# FEV-60_IO_Board.net
KiCad netlist of a schematic drawn in Altium Designer
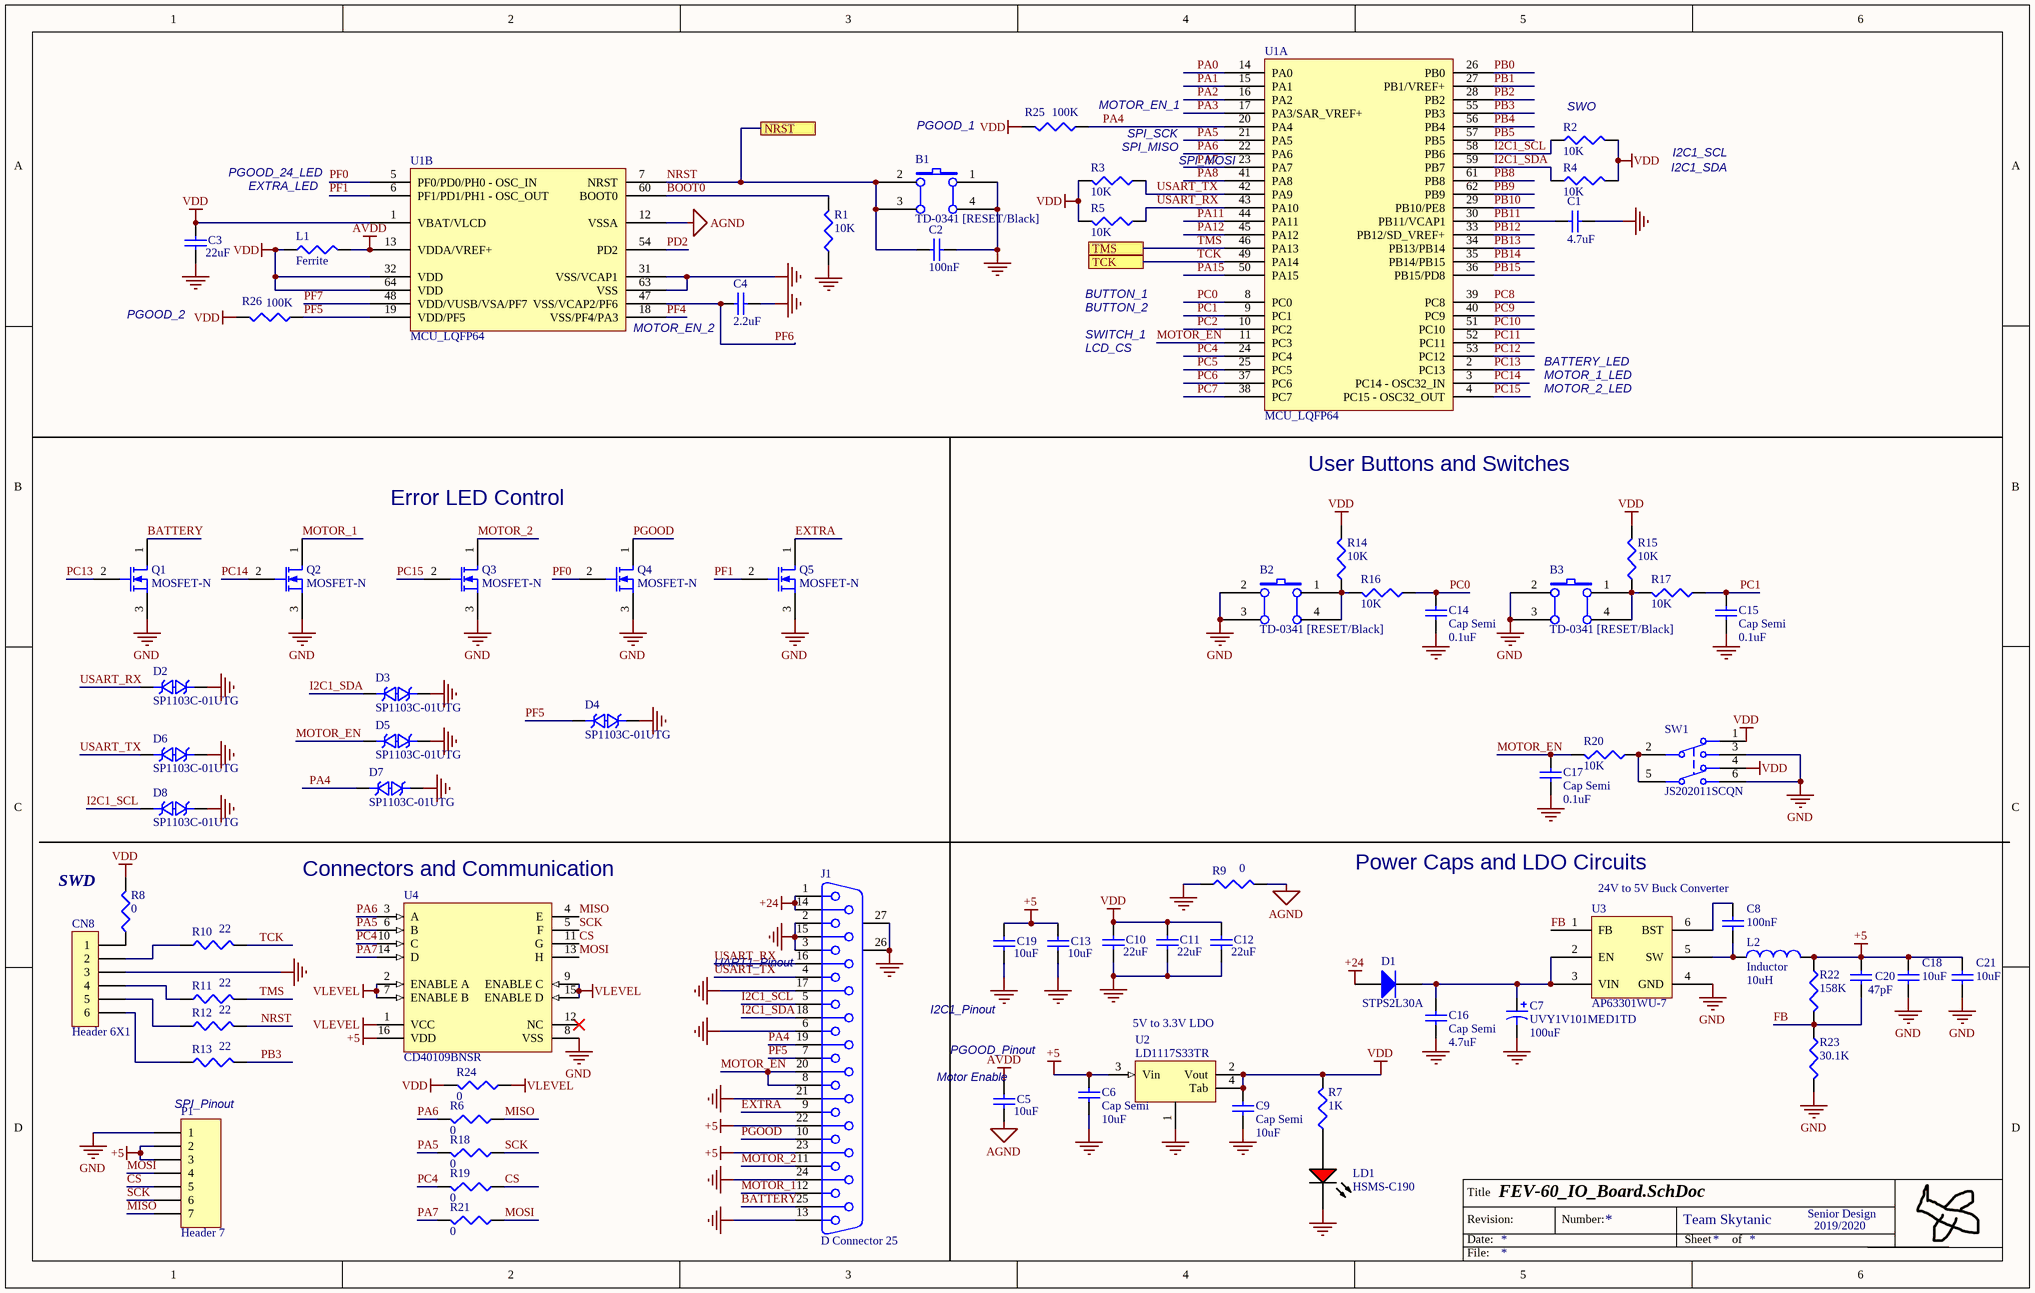
[diagram p0: FEV-60_IO_Board.SchDoc]

(export (version "E")
  (design (tool "Eeschema 10.0.6"))
  (components
    (comp (ref "B1")
      (value "TD-0341 [RESET/Black]")
      (footprint "Button")
      (description "SE PUSHBUTTON")
      (libsource (lib "Documents") (part "SW PUSHBUTTON"))
    )
    (comp (ref "B2")
      (value "TD-0341 [RESET/Black]")
      (footprint "Button")
      (description "SE PUSHBUTTON")
      (libsource (lib "Documents") (part "SW PUSHBUTTON"))
    )
    (comp (ref "B3")
      (value "TD-0341 [RESET/Black]")
      (footprint "Button")
      (description "SE PUSHBUTTON")
      (libsource (lib "Documents") (part "SW PUSHBUTTON"))
    )
    (comp (ref "C1")
      (value "4.7uF")
      (footprint "1608[0603]")
      (description "Capacitor (Semiconductor SIM Model)")
      (fields (field (name "Comment") "Cap Semi") (field (name "PUBLISHER") "Altium Limited"))
      (libsource (lib "Miscellaneous Devices") (part "Cap Semi"))
    )
    (comp (ref "C2")
      (value "100nF")
      (footprint "1608[0603]")
      (description "Capacitor (Semiconductor SIM Model)")
      (fields (field (name "Comment") "Cap Semi") (field (name "PUBLISHER") "Altium Limited"))
      (libsource (lib "Miscellaneous Devices") (part "Cap Semi"))
    )
    (comp (ref "C3")
      (value "22uF")
      (footprint "1608[0603]")
      (description "Capacitor (Semiconductor SIM Model)")
      (fields (field (name "Comment") "Cap Semi") (field (name "PUBLISHER") "Altium Limited"))
      (libsource (lib "Miscellaneous Devices") (part "Cap Semi"))
    )
    (comp (ref "C4")
      (value "2.2uF")
      (footprint "1608[0603]")
      (description "Capacitor (Semiconductor SIM Model)")
      (fields (field (name "Comment") "Cap Semi") (field (name "PUBLISHER") "Altium Limited"))
      (libsource (lib "Miscellaneous Devices") (part "Cap Semi"))
    )
    (comp (ref "C5")
      (value "10uF")
      (footprint "1608[0603]")
      (description "Capacitor (Semiconductor SIM Model)")
      (fields (field (name "Comment") "Cap Semi") (field (name "PUBLISHER") "Altium Limited"))
      (libsource (lib "Miscellaneous Devices") (part "Cap Semi"))
    )
    (comp (ref "C6")
      (value "Cap Semi")
      (footprint "1608[0603]")
      (description "Capacitor (Semiconductor SIM Model)")
      (fields (field (name "ALTIUM_VALUE") "10uF") (field (name "PUBLISHER") "Altium Limited"))
      (libsource (lib "Miscellaneous Devices") (part "Cap Semi"))
    )
    (comp (ref "C7")
      (value "UVY1V101MED1TD")
      (footprint "UVY1V101MED1TD")
      (description "Polarized Capacitor (Axial)")
      (fields (field (name "ALTIUM_VALUE") "100uF") (field (name "PUBLISHER") "Altium Limited"))
      (libsource (lib "FEV-60_Lib") (part "UVY1V101MED1TD"))
    )
    (comp (ref "C8")
      (value "100nF")
      (footprint "1608[0603]")
      (description "Capacitor (Semiconductor SIM Model)")
      (fields (field (name "Comment") "Cap Semi") (field (name "PUBLISHER") "Altium Limited"))
      (libsource (lib "Miscellaneous Devices") (part "Cap Semi"))
    )
    (comp (ref "C9")
      (value "Cap Semi")
      (footprint "1608[0603]")
      (description "Capacitor (Semiconductor SIM Model)")
      (fields (field (name "ALTIUM_VALUE") "10uF") (field (name "PUBLISHER") "Altium Limited"))
      (libsource (lib "Miscellaneous Devices") (part "Cap Semi"))
    )
    (comp (ref "C10")
      (value "22uF")
      (footprint "1608[0603]")
      (description "Capacitor (Semiconductor SIM Model)")
      (fields (field (name "Comment") "Cap Semi") (field (name "PUBLISHER") "Altium Limited"))
      (libsource (lib "Miscellaneous Devices") (part "Cap Semi"))
    )
    (comp (ref "C11")
      (value "22uF")
      (footprint "1608[0603]")
      (description "Capacitor (Semiconductor SIM Model)")
      (fields (field (name "Comment") "Cap Semi") (field (name "PUBLISHER") "Altium Limited"))
      (libsource (lib "Miscellaneous Devices") (part "Cap Semi"))
    )
    (comp (ref "C12")
      (value "22uF")
      (footprint "1608[0603]")
      (description "Capacitor (Semiconductor SIM Model)")
      (fields (field (name "Comment") "Cap Semi") (field (name "PUBLISHER") "Altium Limited"))
      (libsource (lib "Miscellaneous Devices") (part "Cap Semi"))
    )
    (comp (ref "C13")
      (value "10uF")
      (footprint "1608[0603]")
      (description "Capacitor (Semiconductor SIM Model)")
      (fields (field (name "Comment") "Cap Semi") (field (name "PUBLISHER") "Altium Limited"))
      (libsource (lib "Miscellaneous Devices") (part "Cap Semi"))
    )
    (comp (ref "C14")
      (value "Cap Semi")
      (footprint "1608[0603]")
      (description "Capacitor (Semiconductor SIM Model)")
      (fields (field (name "ALTIUM_VALUE") "0.1uF") (field (name "PUBLISHER") "Altium Limited"))
      (libsource (lib "Miscellaneous Devices") (part "Cap Semi"))
    )
    (comp (ref "C15")
      (value "Cap Semi")
      (footprint "1608[0603]")
      (description "Capacitor (Semiconductor SIM Model)")
      (fields (field (name "ALTIUM_VALUE") "0.1uF") (field (name "PUBLISHER") "Altium Limited"))
      (libsource (lib "Miscellaneous Devices") (part "Cap Semi"))
    )
    (comp (ref "C16")
      (value "Cap Semi")
      (footprint "1608[0603]")
      (description "Capacitor (Semiconductor SIM Model)")
      (fields (field (name "ALTIUM_VALUE") "4.7uF") (field (name "PUBLISHER") "Altium Limited"))
      (libsource (lib "Miscellaneous Devices") (part "Cap Semi"))
    )
    (comp (ref "C17")
      (value "Cap Semi")
      (footprint "1608[0603]")
      (description "Capacitor (Semiconductor SIM Model)")
      (fields (field (name "ALTIUM_VALUE") "0.1uF") (field (name "PUBLISHER") "Altium Limited"))
      (libsource (lib "Miscellaneous Devices") (part "Cap Semi"))
    )
    (comp (ref "C18")
      (value "10uF")
      (footprint "1608[0603]")
      (description "Capacitor (Semiconductor SIM Model)")
      (fields (field (name "Comment") "Cap Semi") (field (name "PUBLISHER") "Altium Limited"))
      (libsource (lib "Miscellaneous Devices") (part "Cap Semi"))
    )
    (comp (ref "C19")
      (value "10uF")
      (footprint "1608[0603]")
      (description "Capacitor (Semiconductor SIM Model)")
      (fields (field (name "Comment") "Cap Semi") (field (name "PUBLISHER") "Altium Limited"))
      (libsource (lib "Miscellaneous Devices") (part "Cap Semi"))
    )
    (comp (ref "C20")
      (value "47pF")
      (footprint "1608[0603]")
      (description "Capacitor (Semiconductor SIM Model)")
      (fields (field (name "Comment") "Cap Semi") (field (name "PUBLISHER") "Altium Limited"))
      (libsource (lib "Miscellaneous Devices") (part "Cap Semi"))
    )
    (comp (ref "C21")
      (value "10uF")
      (footprint "1608[0603]")
      (description "Capacitor (Semiconductor SIM Model)")
      (fields (field (name "Comment") "Cap Semi") (field (name "PUBLISHER") "Altium Limited"))
      (libsource (lib "Miscellaneous Devices") (part "Cap Semi"))
    )
    (comp (ref "CN8")
      (value "Header 6X1")
      (footprint "HDR1X6")
      (description "Header, 6-Pin, Single row")
      (fields (field (name "PUBLISHER") "Altium Limited"))
      (libsource (lib "Nucleo_64") (part "Header 6X1"))
    )
    (comp (ref "D1")
      (value "STPS2L30A")
      (footprint "STPS2L30A")
      (libsource (lib "Nucleo_64") (part "STPS2L30A"))
    )
    (comp (ref "D2")
      (value "SP1103C-01UTG")
      (footprint "SP1103C-01UTG")
      (description "9V (Typ) Clamp 80A (8/20µs) Ipp Tvs Diode Surface Mount 2-DFN (1.6x1)")
      (libsource (lib "FEV-60_Lib") (part "SP1103C-01UTG"))
    )
    (comp (ref "D3")
      (value "SP1103C-01UTG")
      (footprint "SP1103C-01UTG")
      (description "9V (Typ) Clamp 80A (8/20µs) Ipp Tvs Diode Surface Mount 2-DFN (1.6x1)")
      (libsource (lib "FEV-60_Lib") (part "SP1103C-01UTG"))
    )
    (comp (ref "D4")
      (value "SP1103C-01UTG")
      (footprint "SP1103C-01UTG")
      (description "9V (Typ) Clamp 80A (8/20µs) Ipp Tvs Diode Surface Mount 2-DFN (1.6x1)")
      (libsource (lib "FEV-60_Lib") (part "SP1103C-01UTG"))
    )
    (comp (ref "D5")
      (value "SP1103C-01UTG")
      (footprint "SP1103C-01UTG")
      (description "9V (Typ) Clamp 80A (8/20µs) Ipp Tvs Diode Surface Mount 2-DFN (1.6x1)")
      (libsource (lib "FEV-60_Lib") (part "SP1103C-01UTG"))
    )
    (comp (ref "D6")
      (value "SP1103C-01UTG")
      (footprint "SP1103C-01UTG")
      (description "9V (Typ) Clamp 80A (8/20µs) Ipp Tvs Diode Surface Mount 2-DFN (1.6x1)")
      (libsource (lib "FEV-60_Lib") (part "SP1103C-01UTG"))
    )
    (comp (ref "D7")
      (value "SP1103C-01UTG")
      (footprint "SP1103C-01UTG")
      (description "9V (Typ) Clamp 80A (8/20µs) Ipp Tvs Diode Surface Mount 2-DFN (1.6x1)")
      (libsource (lib "FEV-60_Lib") (part "SP1103C-01UTG"))
    )
    (comp (ref "D8")
      (value "SP1103C-01UTG")
      (footprint "SP1103C-01UTG")
      (description "9V (Typ) Clamp 80A (8/20µs) Ipp Tvs Diode Surface Mount 2-DFN (1.6x1)")
      (libsource (lib "FEV-60_Lib") (part "SP1103C-01UTG"))
    )
    (comp (ref "J1")
      (value "D Connector 25")
      (footprint "DSUB1.385-2H25A")
      (description "Receptacle Assembly, 25 Position, Right Angle")
      (fields (field (name "PUBLISHER") "Altium Limited"))
      (libsource (lib "Miscellaneous Connectors") (part "D Connector 25"))
    )
    (comp (ref "L1")
      (value "Ferrite")
      (footprint "J1-0603")
      (description "Resistor")
      (fields (field (name "PUBLISHER") "Altium Limited"))
      (libsource (lib "Miscellaneous Devices") (part "Res3"))
    )
    (comp (ref "L2")
      (value "Inductor")
      (footprint "74404084100")
      (fields (field (name "ALTIUM_VALUE") "10uH") (field (name "PUBLISHER") "Altium Limited"))
      (libsource (lib "Miscellaneous Devices") (part "Inductor"))
    )
    (comp (ref "LD1")
      (value "HSMS-C190")
      (footprint "AVAG-HSMX-C190_V")
      (description "LED Uni-Color Red, 52 mW, 20 mA, -40 to 85 degC, 2-Pin SMD, RoHS, Tape and Reel")
      (fields (field (name "MANUFACTURER") "Avago"))
      (libsource (lib "Altium Content Vault") (part "LED-RED-AK-2"))
    )
    (comp (ref "P1")
      (value "Header 7")
      (footprint "HDR1X7")
      (description "Header, 7-Pin")
      (fields (field (name "PUBLISHER") "Altium Limited"))
      (libsource (lib "Miscellaneous Connectors") (part "Header 7"))
    )
    (comp (ref "Q1")
      (value "MOSFET-N")
      (footprint "RK7002BMT116")
      (description "N-Channel MOSFET")
      (fields (field (name "PUBLISHER") "Altium Limited"))
      (libsource (lib "Miscellaneous Devices") (part "MOSFET-N"))
    )
    (comp (ref "Q2")
      (value "MOSFET-N")
      (footprint "RK7002BMT116")
      (description "N-Channel MOSFET")
      (fields (field (name "PUBLISHER") "Altium Limited"))
      (libsource (lib "Miscellaneous Devices") (part "MOSFET-N"))
    )
    (comp (ref "Q3")
      (value "MOSFET-N")
      (footprint "RK7002BMT116")
      (description "N-Channel MOSFET")
      (fields (field (name "PUBLISHER") "Altium Limited"))
      (libsource (lib "Miscellaneous Devices") (part "MOSFET-N"))
    )
    (comp (ref "Q4")
      (value "MOSFET-N")
      (footprint "RK7002BMT116")
      (description "N-Channel MOSFET")
      (fields (field (name "PUBLISHER") "Altium Limited"))
      (libsource (lib "Miscellaneous Devices") (part "MOSFET-N"))
    )
    (comp (ref "Q5")
      (value "MOSFET-N")
      (footprint "RK7002BMT116")
      (description "N-Channel MOSFET")
      (fields (field (name "PUBLISHER") "Altium Limited"))
      (libsource (lib "Miscellaneous Devices") (part "MOSFET-N"))
    )
    (comp (ref "R1")
      (value "10K")
      (footprint "J1-0603")
      (description "Resistor")
      (fields (field (name "Comment") "Res3") (field (name "PUBLISHER") "Altium Limited"))
      (libsource (lib "Miscellaneous Devices") (part "Res3"))
    )
    (comp (ref "R2")
      (value "10K")
      (footprint "J1-0603")
      (description "Resistor")
      (fields (field (name "Comment") "Res3") (field (name "PUBLISHER") "Altium Limited"))
      (libsource (lib "Miscellaneous Devices") (part "Res3"))
    )
    (comp (ref "R3")
      (value "10K")
      (footprint "J1-0603")
      (description "Resistor")
      (fields (field (name "Comment") "Res3") (field (name "PUBLISHER") "Altium Limited"))
      (libsource (lib "Miscellaneous Devices") (part "Res3"))
    )
    (comp (ref "R4")
      (value "10K")
      (footprint "J1-0603")
      (description "Resistor")
      (fields (field (name "Comment") "Res3") (field (name "PUBLISHER") "Altium Limited"))
      (libsource (lib "Miscellaneous Devices") (part "Res3"))
    )
    (comp (ref "R5")
      (value "10K")
      (footprint "J1-0603")
      (description "Resistor")
      (fields (field (name "Comment") "Res3") (field (name "PUBLISHER") "Altium Limited"))
      (libsource (lib "Miscellaneous Devices") (part "Res3"))
    )
    (comp (ref "R6")
      (value "0")
      (footprint "J1-0603")
      (description "Resistor")
      (fields (field (name "Comment") "Res3") (field (name "PUBLISHER") "Altium Limited"))
      (libsource (lib "Miscellaneous Devices") (part "Res3"))
    )
    (comp (ref "R7")
      (value "1K")
      (footprint "J1-0603")
      (description "Resistor")
      (fields (field (name "Comment") "Res3") (field (name "PUBLISHER") "Altium Limited"))
      (libsource (lib "Miscellaneous Devices") (part "Res3"))
    )
    (comp (ref "R8")
      (value "0")
      (footprint "J1-0603")
      (description "Resistor")
      (fields (field (name "Comment") "Res3") (field (name "PUBLISHER") "Altium Limited"))
      (libsource (lib "Miscellaneous Devices") (part "Res3"))
    )
    (comp (ref "R9")
      (value "0")
      (footprint "J1-0603")
      (description "Resistor")
      (fields (field (name "Comment") "Res3") (field (name "PUBLISHER") "Altium Limited"))
      (libsource (lib "Miscellaneous Devices") (part "Res3"))
    )
    (comp (ref "R10")
      (value "22")
      (footprint "J1-0603")
      (description "Resistor")
      (fields (field (name "Comment") "Res3") (field (name "PUBLISHER") "Altium Limited"))
      (libsource (lib "Miscellaneous Devices") (part "Res3"))
    )
    (comp (ref "R11")
      (value "22")
      (footprint "J1-0603")
      (description "Resistor")
      (fields (field (name "Comment") "Res3") (field (name "PUBLISHER") "Altium Limited"))
      (libsource (lib "Miscellaneous Devices") (part "Res3"))
    )
    (comp (ref "R12")
      (value "22")
      (footprint "J1-0603")
      (description "Resistor")
      (fields (field (name "Comment") "Res3") (field (name "PUBLISHER") "Altium Limited"))
      (libsource (lib "Miscellaneous Devices") (part "Res3"))
    )
    (comp (ref "R13")
      (value "22")
      (footprint "J1-0603")
      (description "Resistor")
      (fields (field (name "Comment") "Res3") (field (name "PUBLISHER") "Altium Limited"))
      (libsource (lib "Miscellaneous Devices") (part "Res3"))
    )
    (comp (ref "R14")
      (value "10K")
      (footprint "J1-0603")
      (description "Resistor")
      (fields (field (name "Comment") "Res3") (field (name "PUBLISHER") "Altium Limited"))
      (libsource (lib "Miscellaneous Devices") (part "Res3"))
    )
    (comp (ref "R15")
      (value "10K")
      (footprint "J1-0603")
      (description "Resistor")
      (fields (field (name "Comment") "Res3") (field (name "PUBLISHER") "Altium Limited"))
      (libsource (lib "Miscellaneous Devices") (part "Res3"))
    )
    (comp (ref "R16")
      (value "10K")
      (footprint "J1-0603")
      (description "Resistor")
      (fields (field (name "Comment") "Res3") (field (name "PUBLISHER") "Altium Limited"))
      (libsource (lib "Miscellaneous Devices") (part "Res3"))
    )
    (comp (ref "R17")
      (value "10K")
      (footprint "J1-0603")
      (description "Resistor")
      (fields (field (name "Comment") "Res3") (field (name "PUBLISHER") "Altium Limited"))
      (libsource (lib "Miscellaneous Devices") (part "Res3"))
    )
    (comp (ref "R18")
      (value "0")
      (footprint "J1-0603")
      (description "Resistor")
      (fields (field (name "Comment") "Res3") (field (name "PUBLISHER") "Altium Limited"))
      (libsource (lib "Miscellaneous Devices") (part "Res3"))
    )
    (comp (ref "R19")
      (value "0")
      (footprint "J1-0603")
      (description "Resistor")
      (fields (field (name "Comment") "Res3") (field (name "PUBLISHER") "Altium Limited"))
      (libsource (lib "Miscellaneous Devices") (part "Res3"))
    )
    (comp (ref "R20")
      (value "10K")
      (footprint "J1-0603")
      (description "Resistor")
      (fields (field (name "Comment") "Res3") (field (name "PUBLISHER") "Altium Limited"))
      (libsource (lib "Miscellaneous Devices") (part "Res3"))
    )
    (comp (ref "R21")
      (value "0")
      (footprint "J1-0603")
      (description "Resistor")
      (fields (field (name "Comment") "Res3") (field (name "PUBLISHER") "Altium Limited"))
      (libsource (lib "Miscellaneous Devices") (part "Res3"))
    )
    (comp (ref "R22")
      (value "158K")
      (footprint "J1-0603")
      (description "Resistor")
      (fields (field (name "Comment") "Res3") (field (name "PUBLISHER") "Altium Limited"))
      (libsource (lib "Miscellaneous Devices") (part "Res3"))
    )
    (comp (ref "R23")
      (value "30.1K")
      (footprint "J1-0603")
      (description "Resistor")
      (fields (field (name "Comment") "Res3") (field (name "PUBLISHER") "Altium Limited"))
      (libsource (lib "Miscellaneous Devices") (part "Res3"))
    )
    (comp (ref "R24")
      (value "0")
      (footprint "J1-0603")
      (description "Resistor")
      (fields (field (name "Comment") "Res3") (field (name "PUBLISHER") "Altium Limited"))
      (libsource (lib "Miscellaneous Devices") (part "Res3"))
    )
    (comp (ref "R25")
      (value "100K")
      (footprint "J1-0603")
      (description "Resistor")
      (fields (field (name "Comment") "Res3") (field (name "PUBLISHER") "Altium Limited"))
      (libsource (lib "Miscellaneous Devices") (part "Res3"))
    )
    (comp (ref "R26")
      (value "100K")
      (footprint "J1-0603")
      (description "Resistor")
      (fields (field (name "Comment") "Res3") (field (name "PUBLISHER") "Altium Limited"))
      (libsource (lib "Miscellaneous Devices") (part "Res3"))
    )
    (comp (ref "SW1")
      (value "JS202011SCQN")
      (footprint "CKCP-JS202011SCQN-6_V")
      (description "Switch Slide DPDT, 0.3 A, 6 V, -40 to 85 degC, 6-Pin SMD, RoHS, Tape and Reel")
      (fields (field (name "MANUFACTURER") "C&K Components"))
      (libsource (lib "Altium Content Vault") (part "CKCP-JS202011SCQN-6"))
    )
    (comp (ref "U1")
      (value "MCU_LQFP64")
      (footprint "STM32F030R8")
      (libsource (lib "Nucleo_64") (part "MCU_LQFP64"))
    )
    (comp (ref "U2")
      (value "LD1117S33TR")
      (footprint "LD1117S33TR")
      (libsource (lib "mb1045") (part "LD1117"))
    )
    (comp (ref "U3")
      (value "AP63301WU-7")
      (footprint "AP63301WU-7")
      (description "Buck Switching Regulator IC Positive Adjustable 0.8V 1 Output 3A SOT-23-6 Thin, TSOT-23-6")
      (libsource (lib "2020-01-14_19-20-40") (part "AP63301WU-7"))
    )
    (comp (ref "U4")
      (value "CD40109BNSR")
      (footprint "NS0016A_N")
      (fields (field (name "MANUFACTURER") "Texas Instruments"))
      (libsource (lib "Altium Content Vault") (part "TI-CD40109B-16"))
    )
  )
  (nets
    (net (code "1") (name "+5") (class "Default")
      (node (ref "C13") (pin "2") (pinfunction "2_2") (pintype "passive"))
      (node (ref "C18") (pin "2") (pinfunction "2_2") (pintype "passive"))
      (node (ref "C19") (pin "2") (pinfunction "2_2") (pintype "passive"))
      (node (ref "C20") (pin "2") (pinfunction "2_2") (pintype "passive"))
      (node (ref "C21") (pin "2") (pinfunction "2_2") (pintype "passive"))
      (node (ref "C6") (pin "2") (pinfunction "2_2") (pintype "passive"))
      (node (ref "J1") (pin "22") (pinfunction "22_22") (pintype "passive"))
      (node (ref "J1") (pin "23") (pinfunction "23_23") (pintype "passive"))
      (node (ref "L2") (pin "2") (pinfunction "2_2") (pintype "passive"))
      (node (ref "P1") (pin "2") (pinfunction "2_2") (pintype "passive"))
      (node (ref "P1") (pin "3") (pinfunction "3_3") (pintype "passive"))
      (node (ref "R22") (pin "1") (pinfunction "1_1") (pintype "passive"))
      (node (ref "U2") (pin "3") (pinfunction "Vin_3") (pintype "input"))
      (node (ref "U4") (pin "16") (pinfunction "VDD_16") (pintype "power_in"))
    )
    (net (code "2") (name "+24") (class "Default")
      (node (ref "D1") (pin "1") (pinfunction "A_1") (pintype "passive"))
      (node (ref "J1") (pin "1") (pinfunction "1_1") (pintype "passive"))
      (node (ref "J1") (pin "14") (pinfunction "14_14") (pintype "passive"))
    )
    (net (code "3") (name "/BATTERY") (class "Default")
      (node (ref "J1") (pin "25") (pinfunction "25_25") (pintype "passive"))
      (node (ref "Q1") (pin "1") (pinfunction "D_1") (pintype "passive"))
    )
    (net (code "4") (name "/BOOT0") (class "Default")
      (node (ref "R1") (pin "2") (pinfunction "2_2") (pintype "passive"))
      (node (ref "U1") (pin "60") (pinfunction "BOOT0_60") (pintype "passive"))
    )
    (net (code "5") (name "/CS") (class "Default")
      (node (ref "P1") (pin "5") (pinfunction "5_5") (pintype "passive"))
      (node (ref "R19") (pin "1") (pinfunction "1_1") (pintype "passive"))
      (node (ref "U4") (pin "11") (pinfunction "G_11") (pintype "tri_state"))
    )
    (net (code "6") (name "/EXTRA") (class "Default")
      (node (ref "J1") (pin "9") (pinfunction "9_9") (pintype "passive"))
      (node (ref "Q5") (pin "1") (pinfunction "D_1") (pintype "passive"))
    )
    (net (code "7") (name "/FB") (class "Default")
      (node (ref "C20") (pin "1") (pinfunction "1_1") (pintype "passive"))
      (node (ref "R22") (pin "2") (pinfunction "2_2") (pintype "passive"))
      (node (ref "R23") (pin "1") (pinfunction "1_1") (pintype "passive"))
      (node (ref "U3") (pin "1") (pinfunction "FB_1") (pintype "passive"))
    )
    (net (code "8") (name "/I2C1_SCL") (class "Default")
      (node (ref "D8") (pin "2") (pinfunction "K_2") (pintype "passive"))
      (node (ref "J1") (pin "5") (pinfunction "5_5") (pintype "passive"))
      (node (ref "R2") (pin "1") (pinfunction "1_1") (pintype "passive"))
      (node (ref "U1") (pin "58") (pinfunction "PB6_58") (pintype "passive"))
    )
    (net (code "9") (name "/I2C1_SDA") (class "Default")
      (node (ref "D3") (pin "2") (pinfunction "K_2") (pintype "passive"))
      (node (ref "J1") (pin "18") (pinfunction "18_18") (pintype "passive"))
      (node (ref "R4") (pin "1") (pinfunction "1_1") (pintype "passive"))
      (node (ref "U1") (pin "59") (pinfunction "PB7_59") (pintype "passive"))
    )
    (net (code "10") (name "/MISO") (class "Default")
      (node (ref "P1") (pin "7") (pinfunction "7_7") (pintype "passive"))
      (node (ref "R6") (pin "1") (pinfunction "1_1") (pintype "passive"))
      (node (ref "U4") (pin "4") (pinfunction "E_4") (pintype "tri_state"))
    )
    (net (code "11") (name "/MOSI") (class "Default")
      (node (ref "P1") (pin "4") (pinfunction "4_4") (pintype "passive"))
      (node (ref "R21") (pin "1") (pinfunction "1_1") (pintype "passive"))
      (node (ref "U4") (pin "13") (pinfunction "H_13") (pintype "tri_state"))
    )
    (net (code "12") (name "/MOTOR_1") (class "Default")
      (node (ref "J1") (pin "12") (pinfunction "12_12") (pintype "passive"))
      (node (ref "Q2") (pin "1") (pinfunction "D_1") (pintype "passive"))
    )
    (net (code "13") (name "/MOTOR_2") (class "Default")
      (node (ref "J1") (pin "11") (pinfunction "11_11") (pintype "passive"))
      (node (ref "Q3") (pin "1") (pinfunction "D_1") (pintype "passive"))
    )
    (net (code "14") (name "/MOTOR_EN") (class "Default")
      (node (ref "C17") (pin "2") (pinfunction "2_2") (pintype "passive"))
      (node (ref "D5") (pin "2") (pinfunction "K_2") (pintype "passive"))
      (node (ref "J1") (pin "20") (pinfunction "20_20") (pintype "passive"))
      (node (ref "J1") (pin "8") (pinfunction "8_8") (pintype "passive"))
      (node (ref "R20") (pin "2") (pinfunction "2_2") (pintype "passive"))
      (node (ref "U1") (pin "11") (pinfunction "PC3_11") (pintype "passive"))
    )
    (net (code "15") (name "/NRST") (class "Default")
      (node (ref "B1") (pin "2") (pinfunction "B0_2") (pintype "passive"))
      (node (ref "B1") (pin "3") (pinfunction "B1_3") (pintype "passive"))
      (node (ref "C2") (pin "2") (pinfunction "2_2") (pintype "passive"))
      (node (ref "R12") (pin "2") (pinfunction "2_2") (pintype "passive"))
      (node (ref "U1") (pin "7") (pinfunction "NRST_7") (pintype "passive"))
    )
    (net (code "16") (name "/PA0") (class "Default")
      (node (ref "U1") (pin "14") (pinfunction "PA0_14") (pintype "passive"))
    )
    (net (code "17") (name "/PA1") (class "Default")
      (node (ref "U1") (pin "15") (pinfunction "PA1_15") (pintype "passive"))
    )
    (net (code "18") (name "/PA2") (class "Default")
      (node (ref "U1") (pin "16") (pinfunction "PA2_16") (pintype "passive"))
    )
    (net (code "19") (name "/PA3") (class "Default")
      (node (ref "U1") (pin "17") (pinfunction "PA3/SAR_VREF+_17") (pintype "passive"))
    )
    (net (code "20") (name "/PA4") (class "Default")
      (node (ref "D7") (pin "2") (pinfunction "K_2") (pintype "passive"))
      (node (ref "J1") (pin "19") (pinfunction "19_19") (pintype "passive"))
      (node (ref "R25") (pin "1") (pinfunction "1_1") (pintype "passive"))
      (node (ref "U1") (pin "20") (pinfunction "PA4_20") (pintype "passive"))
    )
    (net (code "21") (name "/PA5") (class "Default")
      (node (ref "R18") (pin "2") (pinfunction "2_2") (pintype "passive"))
      (node (ref "U1") (pin "21") (pinfunction "PA5_21") (pintype "passive"))
      (node (ref "U4") (pin "6") (pinfunction "B_6") (pintype "input"))
    )
    (net (code "22") (name "/PA6") (class "Default")
      (node (ref "R6") (pin "2") (pinfunction "2_2") (pintype "passive"))
      (node (ref "U1") (pin "22") (pinfunction "PA6_22") (pintype "passive"))
      (node (ref "U4") (pin "3") (pinfunction "A_3") (pintype "input"))
    )
    (net (code "23") (name "/PA7") (class "Default")
      (node (ref "R21") (pin "2") (pinfunction "2_2") (pintype "passive"))
      (node (ref "U1") (pin "23") (pinfunction "PA7_23") (pintype "passive"))
      (node (ref "U4") (pin "14") (pinfunction "D_14") (pintype "input"))
    )
    (net (code "24") (name "/PA8") (class "Default")
      (node (ref "U1") (pin "41") (pinfunction "PA8_41") (pintype "passive"))
    )
    (net (code "25") (name "/PA11") (class "Default")
      (node (ref "U1") (pin "44") (pinfunction "PA11_44") (pintype "passive"))
    )
    (net (code "26") (name "/PA12") (class "Default")
      (node (ref "U1") (pin "45") (pinfunction "PA12_45") (pintype "passive"))
    )
    (net (code "27") (name "/PA15") (class "Default")
      (node (ref "U1") (pin "50") (pinfunction "PA15_50") (pintype "passive"))
    )
    (net (code "28") (name "/PB0") (class "Default")
      (node (ref "U1") (pin "26") (pinfunction "PB0_26") (pintype "passive"))
    )
    (net (code "29") (name "/PB1") (class "Default")
      (node (ref "U1") (pin "27") (pinfunction "PB1/VREF+_27") (pintype "passive"))
    )
    (net (code "30") (name "/PB2") (class "Default")
      (node (ref "U1") (pin "28") (pinfunction "PB2_28") (pintype "passive"))
    )
    (net (code "31") (name "/PB3") (class "Default")
      (node (ref "R13") (pin "2") (pinfunction "2_2") (pintype "passive"))
      (node (ref "U1") (pin "55") (pinfunction "PB3_55") (pintype "passive"))
    )
    (net (code "32") (name "/PB4") (class "Default")
      (node (ref "U1") (pin "56") (pinfunction "PB4_56") (pintype "passive"))
    )
    (net (code "33") (name "/PB5") (class "Default")
      (node (ref "U1") (pin "57") (pinfunction "PB5_57") (pintype "passive"))
    )
    (net (code "34") (name "/PB8") (class "Default")
      (node (ref "U1") (pin "61") (pinfunction "PB8_61") (pintype "passive"))
    )
    (net (code "35") (name "/PB9") (class "Default")
      (node (ref "U1") (pin "62") (pinfunction "PB9_62") (pintype "passive"))
    )
    (net (code "36") (name "/PB10") (class "Default")
      (node (ref "U1") (pin "29") (pinfunction "PB10/PE8_29") (pintype "passive"))
    )
    (net (code "37") (name "/PB11") (class "Default")
      (node (ref "C1") (pin "2") (pinfunction "2_2") (pintype "passive"))
      (node (ref "U1") (pin "30") (pinfunction "PB11/VCAP1_30") (pintype "passive"))
    )
    (net (code "38") (name "/PB12") (class "Default")
      (node (ref "U1") (pin "33") (pinfunction "PB12/SD_VREF+_33") (pintype "passive"))
    )
    (net (code "39") (name "/PB13") (class "Default")
      (node (ref "U1") (pin "34") (pinfunction "PB13/PB14_34") (pintype "passive"))
    )
    (net (code "40") (name "/PB14") (class "Default")
      (node (ref "U1") (pin "35") (pinfunction "PB14/PB15_35") (pintype "passive"))
    )
    (net (code "41") (name "/PB15") (class "Default")
      (node (ref "U1") (pin "36") (pinfunction "PB15/PD8_36") (pintype "passive"))
    )
    (net (code "42") (name "/PC0") (class "Default")
      (node (ref "C14") (pin "2") (pinfunction "2_2") (pintype "passive"))
      (node (ref "R16") (pin "1") (pinfunction "1_1") (pintype "passive"))
      (node (ref "U1") (pin "8") (pinfunction "PC0_8") (pintype "passive"))
    )
    (net (code "43") (name "/PC1") (class "Default")
      (node (ref "C15") (pin "2") (pinfunction "2_2") (pintype "passive"))
      (node (ref "R17") (pin "1") (pinfunction "1_1") (pintype "passive"))
      (node (ref "U1") (pin "9") (pinfunction "PC1_9") (pintype "passive"))
    )
    (net (code "44") (name "/PC2") (class "Default")
      (node (ref "U1") (pin "10") (pinfunction "PC2_10") (pintype "passive"))
    )
    (net (code "45") (name "/PC4") (class "Default")
      (node (ref "R19") (pin "2") (pinfunction "2_2") (pintype "passive"))
      (node (ref "U1") (pin "24") (pinfunction "PC4_24") (pintype "passive"))
      (node (ref "U4") (pin "10") (pinfunction "C_10") (pintype "input"))
    )
    (net (code "46") (name "/PC5") (class "Default")
      (node (ref "U1") (pin "25") (pinfunction "PC5_25") (pintype "passive"))
    )
    (net (code "47") (name "/PC6") (class "Default")
      (node (ref "U1") (pin "37") (pinfunction "PC6_37") (pintype "passive"))
    )
    (net (code "48") (name "/PC7") (class "Default")
      (node (ref "U1") (pin "38") (pinfunction "PC7_38") (pintype "passive"))
    )
    (net (code "49") (name "/PC8") (class "Default")
      (node (ref "U1") (pin "39") (pinfunction "PC8_39") (pintype "passive"))
    )
    (net (code "50") (name "/PC9") (class "Default")
      (node (ref "U1") (pin "40") (pinfunction "PC9_40") (pintype "passive"))
    )
    (net (code "51") (name "/PC10") (class "Default")
      (node (ref "U1") (pin "51") (pinfunction "PC10_51") (pintype "passive"))
    )
    (net (code "52") (name "/PC11") (class "Default")
      (node (ref "U1") (pin "52") (pinfunction "PC11_52") (pintype "passive"))
    )
    (net (code "53") (name "/PC12") (class "Default")
      (node (ref "U1") (pin "53") (pinfunction "PC12_53") (pintype "passive"))
    )
    (net (code "54") (name "/PC13") (class "Default")
      (node (ref "Q1") (pin "2") (pinfunction "G_2") (pintype "passive"))
      (node (ref "U1") (pin "2") (pinfunction "PC13_2") (pintype "passive"))
    )
    (net (code "55") (name "/PC14") (class "Default")
      (node (ref "Q2") (pin "2") (pinfunction "G_2") (pintype "passive"))
      (node (ref "U1") (pin "3") (pinfunction "PC14_-_OSC32_IN_3") (pintype "passive"))
    )
    (net (code "56") (name "/PC15") (class "Default")
      (node (ref "Q3") (pin "2") (pinfunction "G_2") (pintype "passive"))
      (node (ref "U1") (pin "4") (pinfunction "PC15_-_OSC32_OUT_4") (pintype "passive"))
    )
    (net (code "57") (name "/PD2") (class "Default")
      (node (ref "U1") (pin "54") (pinfunction "PD2_54") (pintype "passive"))
    )
    (net (code "58") (name "/PF0") (class "Default")
      (node (ref "Q4") (pin "2") (pinfunction "G_2") (pintype "passive"))
      (node (ref "U1") (pin "5") (pinfunction "PF0/PD0/PH0_-_OSC_IN_5") (pintype "passive"))
    )
    (net (code "59") (name "/PF1") (class "Default")
      (node (ref "Q5") (pin "2") (pinfunction "G_2") (pintype "passive"))
      (node (ref "U1") (pin "6") (pinfunction "PF1/PD1/PH1_-_OSC_OUT_6") (pintype "passive"))
    )
    (net (code "60") (name "/PF4") (class "Default")
      (node (ref "U1") (pin "18") (pinfunction "VSS/PF4/PA3_18") (pintype "passive"))
    )
    (net (code "61") (name "/PF5") (class "Default")
      (node (ref "D4") (pin "2") (pinfunction "K_2") (pintype "passive"))
      (node (ref "J1") (pin "7") (pinfunction "7_7") (pintype "passive"))
      (node (ref "R26") (pin "1") (pinfunction "1_1") (pintype "passive"))
      (node (ref "U1") (pin "19") (pinfunction "VDD/PF5_19") (pintype "passive"))
    )
    (net (code "62") (name "/PF6") (class "Default")
      (node (ref "C4") (pin "2") (pinfunction "2_2") (pintype "passive"))
      (node (ref "U1") (pin "47") (pinfunction "VSS/VCAP2/PF6_47") (pintype "passive"))
    )
    (net (code "63") (name "/PF7") (class "Default")
      (node (ref "U1") (pin "48") (pinfunction "VDD/VUSB/VSA/PF7_48") (pintype "passive"))
    )
    (net (code "64") (name "/PGOOD") (class "Default")
      (node (ref "J1") (pin "10") (pinfunction "10_10") (pintype "passive"))
      (node (ref "Q4") (pin "1") (pinfunction "D_1") (pintype "passive"))
    )
    (net (code "65") (name "/SCK") (class "Default")
      (node (ref "P1") (pin "6") (pinfunction "6_6") (pintype "passive"))
      (node (ref "R18") (pin "1") (pinfunction "1_1") (pintype "passive"))
      (node (ref "U4") (pin "5") (pinfunction "F_5") (pintype "tri_state"))
    )
    (net (code "66") (name "/TCK") (class "Default")
      (node (ref "R10") (pin "2") (pinfunction "2_2") (pintype "passive"))
      (node (ref "U1") (pin "49") (pinfunction "PA14_49") (pintype "passive"))
    )
    (net (code "67") (name "/TMS") (class "Default")
      (node (ref "R11") (pin "2") (pinfunction "2_2") (pintype "passive"))
      (node (ref "U1") (pin "46") (pinfunction "PA13_46") (pintype "passive"))
    )
    (net (code "68") (name "/USART_RX") (class "Default")
      (node (ref "D2") (pin "2") (pinfunction "K_2") (pintype "passive"))
      (node (ref "J1") (pin "16") (pinfunction "16_16") (pintype "passive"))
      (node (ref "R5") (pin "1") (pinfunction "1_1") (pintype "passive"))
      (node (ref "U1") (pin "43") (pinfunction "PA10_43") (pintype "passive"))
    )
    (net (code "69") (name "/USART_TX") (class "Default")
      (node (ref "D6") (pin "2") (pinfunction "K_2") (pintype "passive"))
      (node (ref "J1") (pin "4") (pinfunction "4_4") (pintype "passive"))
      (node (ref "R3") (pin "1") (pinfunction "1_1") (pintype "passive"))
      (node (ref "U1") (pin "42") (pinfunction "PA9_42") (pintype "passive"))
    )
    (net (code "70") (name "AGND") (class "Default")
      (node (ref "C5") (pin "1") (pinfunction "1_1") (pintype "passive"))
      (node (ref "R9") (pin "2") (pinfunction "2_2") (pintype "passive"))
      (node (ref "U1") (pin "12") (pinfunction "VSSA_12") (pintype "passive"))
    )
    (net (code "71") (name "AVDD") (class "Default")
      (node (ref "C5") (pin "2") (pinfunction "2_2") (pintype "passive"))
      (node (ref "L1") (pin "2") (pinfunction "2_2") (pintype "passive"))
      (node (ref "U1") (pin "13") (pinfunction "VDDA/VREF+_13") (pintype "passive"))
    )
    (net (code "72") (name "GND") (class "Default")
      (node (ref "B1") (pin "1") (pinfunction "A0_1") (pintype "passive"))
      (node (ref "B1") (pin "4") (pinfunction "A1_4") (pintype "passive"))
      (node (ref "B2") (pin "2") (pinfunction "B0_2") (pintype "passive"))
      (node (ref "B2") (pin "3") (pinfunction "B1_3") (pintype "passive"))
      (node (ref "B3") (pin "2") (pinfunction "B0_2") (pintype "passive"))
      (node (ref "B3") (pin "3") (pinfunction "B1_3") (pintype "passive"))
      (node (ref "C1") (pin "1") (pinfunction "1_1") (pintype "passive"))
      (node (ref "C10") (pin "1") (pinfunction "1_1") (pintype "passive"))
      (node (ref "C11") (pin "1") (pinfunction "1_1") (pintype "passive"))
      (node (ref "C12") (pin "1") (pinfunction "1_1") (pintype "passive"))
      (node (ref "C13") (pin "1") (pinfunction "1_1") (pintype "passive"))
      (node (ref "C14") (pin "1") (pinfunction "1_1") (pintype "passive"))
      (node (ref "C15") (pin "1") (pinfunction "1_1") (pintype "passive"))
      (node (ref "C16") (pin "1") (pinfunction "1_1") (pintype "passive"))
      (node (ref "C17") (pin "1") (pinfunction "1_1") (pintype "passive"))
      (node (ref "C18") (pin "1") (pinfunction "1_1") (pintype "passive"))
      (node (ref "C19") (pin "1") (pinfunction "1_1") (pintype "passive"))
      (node (ref "C2") (pin "1") (pinfunction "1_1") (pintype "passive"))
      (node (ref "C21") (pin "1") (pinfunction "1_1") (pintype "passive"))
      (node (ref "C3") (pin "1") (pinfunction "1_1") (pintype "passive"))
      (node (ref "C4") (pin "1") (pinfunction "1_1") (pintype "passive"))
      (node (ref "C6") (pin "1") (pinfunction "1_1") (pintype "passive"))
      (node (ref "C7") (pin "2") (pinfunction "2_2") (pintype "passive"))
      (node (ref "C9") (pin "1") (pinfunction "1_1") (pintype "passive"))
      (node (ref "CN8") (pin "3") (pinfunction "3_3") (pintype "passive"))
      (node (ref "D2") (pin "1") (pinfunction "A_1") (pintype "passive"))
      (node (ref "D3") (pin "1") (pinfunction "A_1") (pintype "passive"))
      (node (ref "D4") (pin "1") (pinfunction "A_1") (pintype "passive"))
      (node (ref "D5") (pin "1") (pinfunction "A_1") (pintype "passive"))
      (node (ref "D6") (pin "1") (pinfunction "A_1") (pintype "passive"))
      (node (ref "D7") (pin "1") (pinfunction "A_1") (pintype "passive"))
      (node (ref "D8") (pin "1") (pinfunction "A_1") (pintype "passive"))
      (node (ref "J1") (pin "13") (pinfunction "13_13") (pintype "passive"))
      (node (ref "J1") (pin "15") (pinfunction "15_15") (pintype "passive"))
      (node (ref "J1") (pin "17") (pinfunction "17_17") (pintype "passive"))
      (node (ref "J1") (pin "2") (pinfunction "2_2") (pintype "passive"))
      (node (ref "J1") (pin "21") (pinfunction "21_21") (pintype "passive"))
      (node (ref "J1") (pin "24") (pinfunction "24_24") (pintype "passive"))
      (node (ref "J1") (pin "26") (pinfunction "MH1_26") (pintype "passive"))
      (node (ref "J1") (pin "27") (pinfunction "MH2_27") (pintype "passive"))
      (node (ref "J1") (pin "3") (pinfunction "3_3") (pintype "passive"))
      (node (ref "J1") (pin "6") (pinfunction "6_6") (pintype "passive"))
      (node (ref "LD1") (pin "2") (pinfunction "K_2") (pintype "passive"))
      (node (ref "P1") (pin "1") (pinfunction "1_1") (pintype "passive"))
      (node (ref "Q1") (pin "3") (pinfunction "S_3") (pintype "passive"))
      (node (ref "Q2") (pin "3") (pinfunction "S_3") (pintype "passive"))
      (node (ref "Q3") (pin "3") (pinfunction "S_3") (pintype "passive"))
      (node (ref "Q4") (pin "3") (pinfunction "S_3") (pintype "passive"))
      (node (ref "Q5") (pin "3") (pinfunction "S_3") (pintype "passive"))
      (node (ref "R1") (pin "1") (pinfunction "1_1") (pintype "passive"))
      (node (ref "R23") (pin "2") (pinfunction "2_2") (pintype "passive"))
      (node (ref "R9") (pin "1") (pinfunction "1_1") (pintype "passive"))
      (node (ref "SW1") (pin "3") (pinfunction "3_3") (pintype "passive"))
      (node (ref "SW1") (pin "6") (pinfunction "6_6") (pintype "passive"))
      (node (ref "U1") (pin "31") (pinfunction "VSS/VCAP1_31") (pintype "passive"))
      (node (ref "U1") (pin "63") (pinfunction "VSS_63") (pintype "passive"))
      (node (ref "U2") (pin "1") (pintype "passive"))
      (node (ref "U3") (pin "4") (pinfunction "GND_4") (pintype "passive"))
      (node (ref "U4") (pin "8") (pinfunction "VSS_8") (pintype "power_in"))
    )
    (net (code "73") (name "Net-(B2-A0)") (class "Default")
      (node (ref "B2") (pin "1") (pinfunction "A0_1") (pintype "passive"))
      (node (ref "B2") (pin "4") (pinfunction "A1_4") (pintype "passive"))
      (node (ref "R14") (pin "1") (pinfunction "1_1") (pintype "passive"))
      (node (ref "R16") (pin "2") (pinfunction "2_2") (pintype "passive"))
    )
    (net (code "74") (name "Net-(B3-A0)") (class "Default")
      (node (ref "B3") (pin "1") (pinfunction "A0_1") (pintype "passive"))
      (node (ref "B3") (pin "4") (pinfunction "A1_4") (pintype "passive"))
      (node (ref "R15") (pin "1") (pinfunction "1_1") (pintype "passive"))
      (node (ref "R17") (pin "2") (pinfunction "2_2") (pintype "passive"))
    )
    (net (code "75") (name "Net-(CN8-Pad1)") (class "Default")
      (node (ref "CN8") (pin "1") (pinfunction "1_1") (pintype "passive"))
      (node (ref "R8") (pin "1") (pinfunction "1_1") (pintype "passive"))
    )
    (net (code "76") (name "Net-(CN8-Pad2)") (class "Default")
      (node (ref "CN8") (pin "2") (pinfunction "2_2") (pintype "passive"))
      (node (ref "R10") (pin "1") (pinfunction "1_1") (pintype "passive"))
    )
    (net (code "77") (name "Net-(CN8-Pad4)") (class "Default")
      (node (ref "CN8") (pin "4") (pinfunction "4_4") (pintype "passive"))
      (node (ref "R11") (pin "1") (pinfunction "1_1") (pintype "passive"))
    )
    (net (code "78") (name "Net-(CN8-Pad5)") (class "Default")
      (node (ref "CN8") (pin "5") (pinfunction "5_5") (pintype "passive"))
      (node (ref "R12") (pin "1") (pinfunction "1_1") (pintype "passive"))
    )
    (net (code "79") (name "Net-(CN8-Pad6)") (class "Default")
      (node (ref "CN8") (pin "6") (pinfunction "6_6") (pintype "passive"))
      (node (ref "R13") (pin "1") (pinfunction "1_1") (pintype "passive"))
    )
    (net (code "80") (name "Net-(D1-K)") (class "Default")
      (node (ref "C16") (pin "2") (pinfunction "2_2") (pintype "passive"))
      (node (ref "C7") (pin "1") (pinfunction "1_1") (pintype "passive"))
      (node (ref "D1") (pin "2") (pinfunction "K_2") (pintype "passive"))
      (node (ref "U3") (pin "2") (pinfunction "EN_2") (pintype "passive"))
      (node (ref "U3") (pin "3") (pinfunction "VIN_3") (pintype "passive"))
    )
    (net (code "81") (name "Net-(LD1-A)") (class "Default")
      (node (ref "LD1") (pin "1") (pinfunction "A_1") (pintype "passive"))
      (node (ref "R7") (pin "1") (pinfunction "1_1") (pintype "passive"))
    )
    (net (code "82") (name "Net-(R20-Pad1)") (class "Default")
      (node (ref "R20") (pin "1") (pinfunction "1_1") (pintype "passive"))
      (node (ref "SW1") (pin "2") (pinfunction "COM_2") (pintype "passive"))
      (node (ref "SW1") (pin "5") (pinfunction "COM_5") (pintype "passive"))
    )
    (net (code "83") (name "Net-(U3-BST)") (class "Default")
      (node (ref "C8") (pin "2") (pinfunction "2_2") (pintype "passive"))
      (node (ref "U3") (pin "6") (pinfunction "BST_6") (pintype "passive"))
    )
    (net (code "84") (name "Net-(U3-SW)") (class "Default")
      (node (ref "C8") (pin "1") (pinfunction "1_1") (pintype "passive"))
      (node (ref "L2") (pin "1") (pinfunction "1_1") (pintype "passive"))
      (node (ref "U3") (pin "5") (pinfunction "SW_5") (pintype "passive"))
    )
    (net (code "85") (name "VDD") (class "Default")
      (node (ref "C10") (pin "2") (pinfunction "2_2") (pintype "passive"))
      (node (ref "C11") (pin "2") (pinfunction "2_2") (pintype "passive"))
      (node (ref "C12") (pin "2") (pinfunction "2_2") (pintype "passive"))
      (node (ref "C3") (pin "2") (pinfunction "2_2") (pintype "passive"))
      (node (ref "C9") (pin "2") (pinfunction "2_2") (pintype "passive"))
      (node (ref "L1") (pin "1") (pinfunction "1_1") (pintype "passive"))
      (node (ref "R14") (pin "2") (pinfunction "2_2") (pintype "passive"))
      (node (ref "R15") (pin "2") (pinfunction "2_2") (pintype "passive"))
      (node (ref "R2") (pin "2") (pinfunction "2_2") (pintype "passive"))
      (node (ref "R24") (pin "2") (pinfunction "2_2") (pintype "passive"))
      (node (ref "R25") (pin "2") (pinfunction "2_2") (pintype "passive"))
      (node (ref "R26") (pin "2") (pinfunction "2_2") (pintype "passive"))
      (node (ref "R3") (pin "2") (pinfunction "2_2") (pintype "passive"))
      (node (ref "R4") (pin "2") (pinfunction "2_2") (pintype "passive"))
      (node (ref "R5") (pin "2") (pinfunction "2_2") (pintype "passive"))
      (node (ref "R7") (pin "2") (pinfunction "2_2") (pintype "passive"))
      (node (ref "R8") (pin "2") (pinfunction "2_2") (pintype "passive"))
      (node (ref "SW1") (pin "1") (pinfunction "1_1") (pintype "passive"))
      (node (ref "SW1") (pin "4") (pinfunction "4_4") (pintype "passive"))
      (node (ref "U1") (pin "1") (pinfunction "VBAT/VLCD_1") (pintype "passive"))
      (node (ref "U1") (pin "32") (pinfunction "VDD_32") (pintype "passive"))
      (node (ref "U1") (pin "64") (pinfunction "VDD_64") (pintype "passive"))
      (node (ref "U2") (pin "2") (pinfunction "Vout_2") (pintype "power_in"))
      (node (ref "U2") (pin "4") (pinfunction "Tab_4") (pintype "power_in"))
    )
    (net (code "86") (name "VLEVEL") (class "Default")
      (node (ref "R24") (pin "1") (pinfunction "1_1") (pintype "passive"))
      (node (ref "U4") (pin "1") (pinfunction "VCC_1") (pintype "power_in"))
      (node (ref "U4") (pin "15") (pinfunction "ENABLE_D_15") (pintype "input"))
      (node (ref "U4") (pin "2") (pinfunction "ENABLE_A_2") (pintype "input"))
      (node (ref "U4") (pin "7") (pinfunction "ENABLE_B_7") (pintype "input"))
      (node (ref "U4") (pin "9") (pinfunction "ENABLE_C_9") (pintype "input"))
    )
    (net (code "87") (name "unconnected-(U4-NC-Pad12)") (class "Default")
      (node (ref "U4") (pin "12") (pinfunction "NC_12") (pintype "passive+no_connect"))
    )
  )
)
